# Microcontroller.net
KiCad netlist of a schematic drawn in Altium Designer
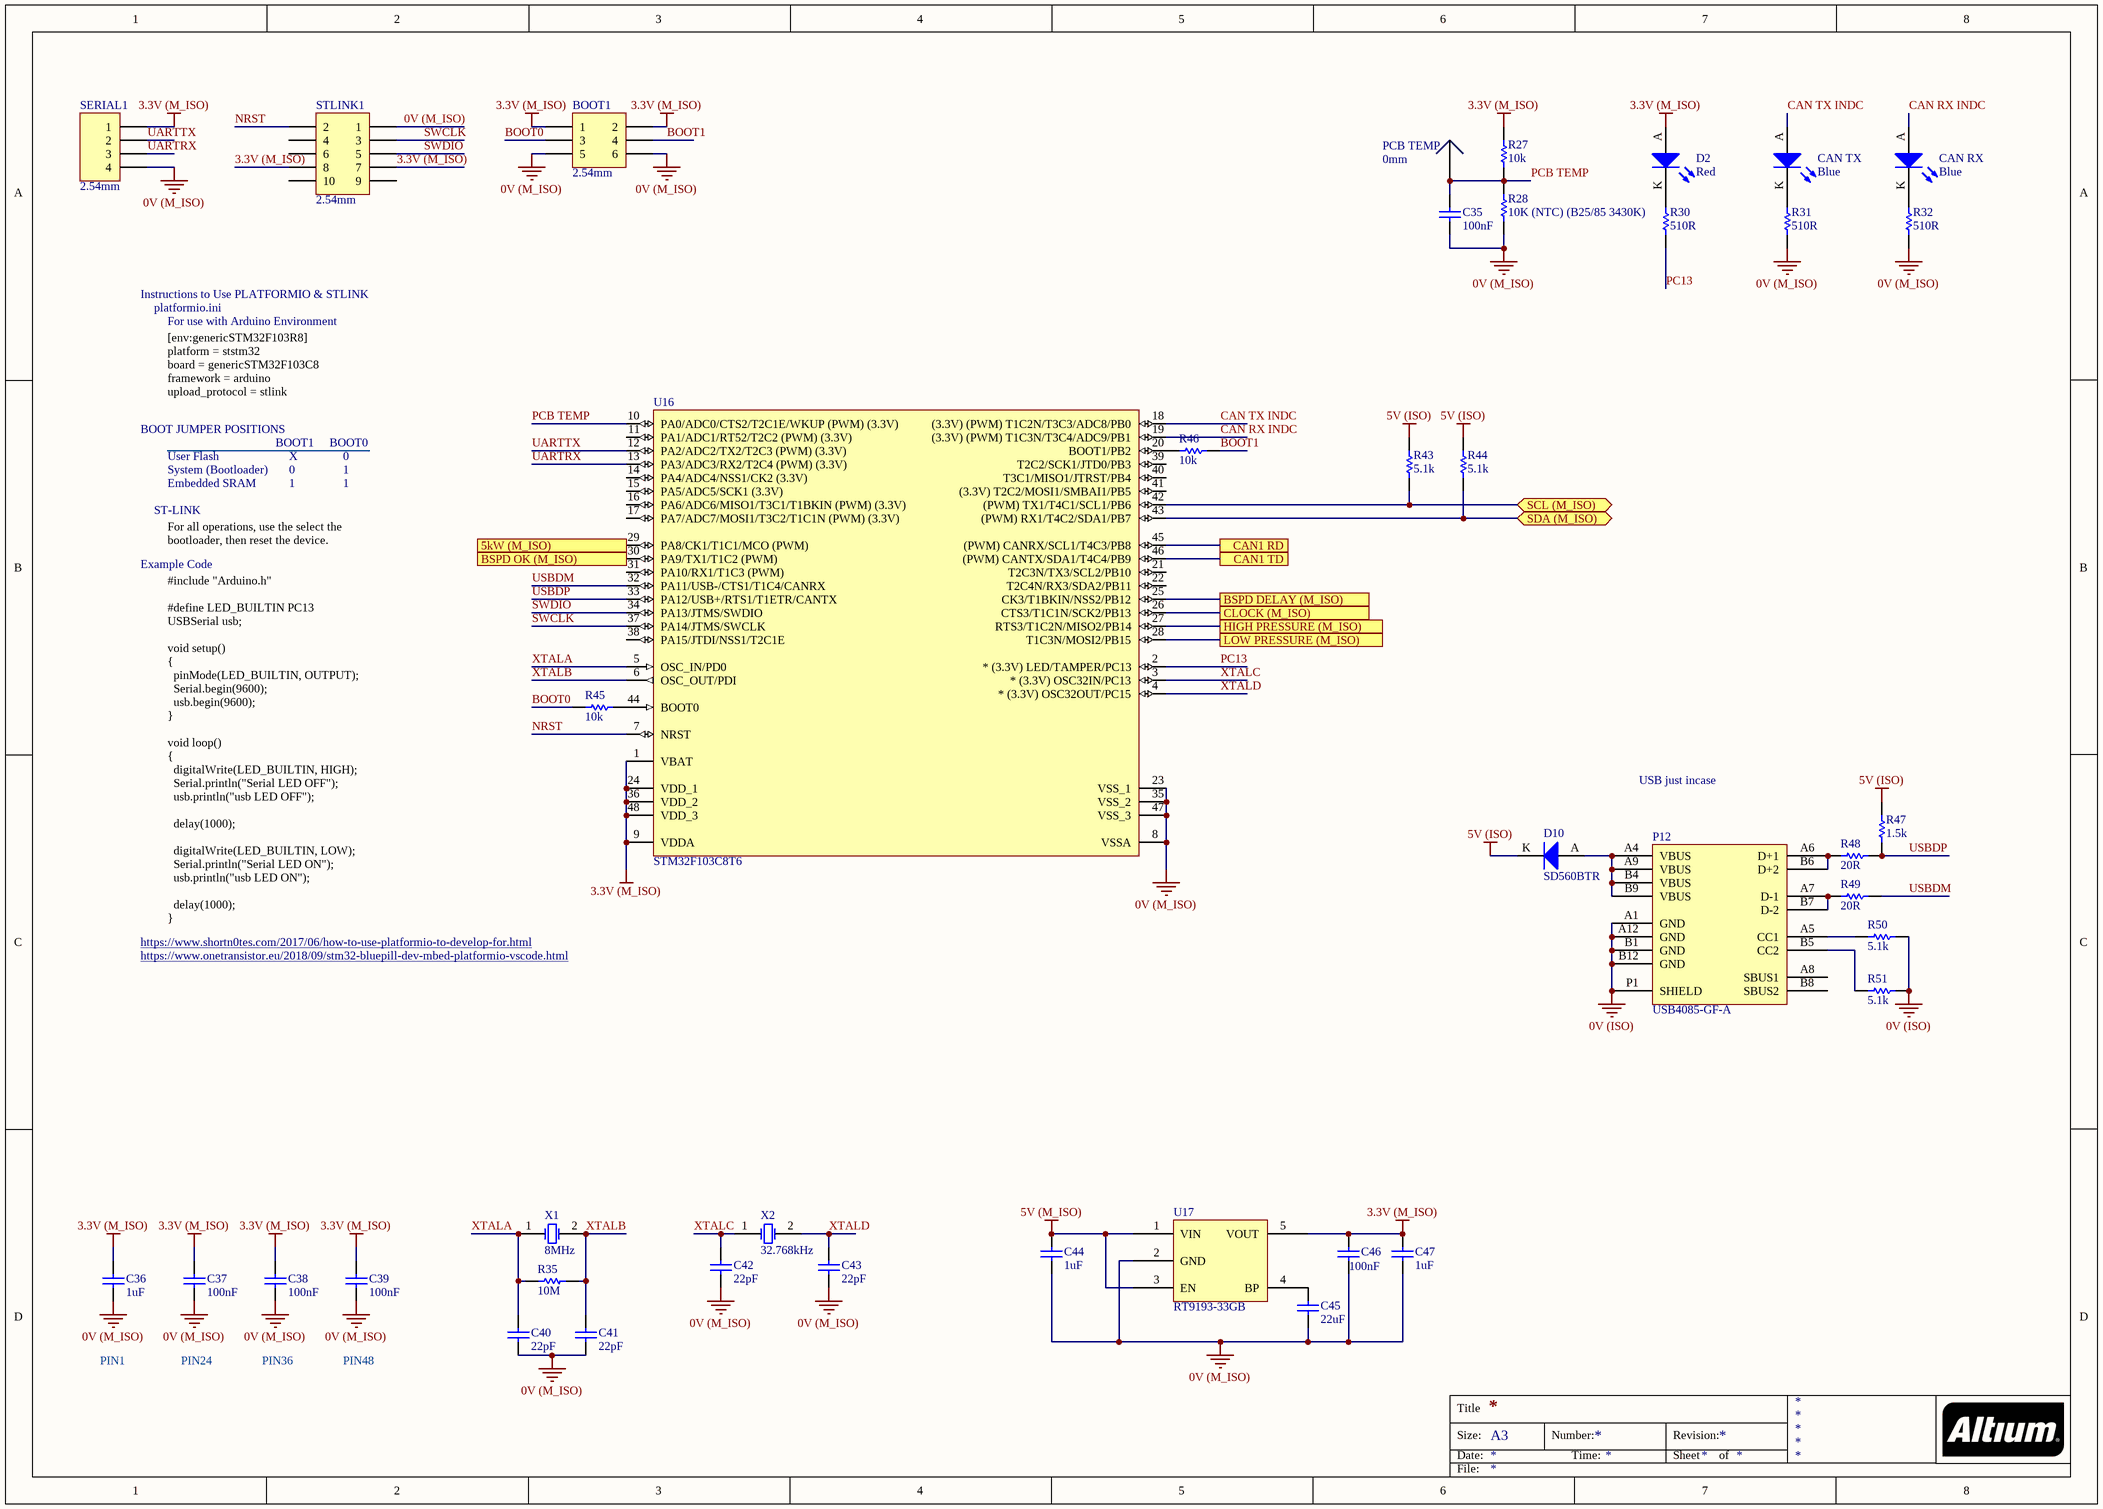
[diagram p0: Microcontroller.SchDoc]

(export (version "E")
  (design (tool "Eeschema 10.0.6"))
  (components
    (comp (ref "BOOT1")
      (value "2.54mm")
      (footprint "TH 2.54mm Header 2x3")
      (fields (field (name "PART NUMBER") "TH 2.54mm Header 2x3") (field (name "CONTACT") "NA"))
      (libsource (lib "ts_20-standard-connectors") (part "Header 2x3"))
    )
    (comp (ref "C35")
      (value "100nF")
      (footprint "0805")
      (fields
        (field (name "PART NUMBER") "GCM21BR71E104KA37L")
        (field (name "TOLERANCE") "10%")
        (field (name "MANUFACTURER") "muRata")
      )
      (libsource (lib "ts_20-standard-library") (part "Capacitor"))
    )
    (comp (ref "C36")
      (value "1uF")
      (footprint "0805")
      (fields
        (field (name "PART NUMBER") "AC0805KKX7R8BB105")
        (field (name "TOLERANCE") "10%")
        (field (name "MANUFACTURER") "YAGEO")
      )
      (libsource (lib "ts_20-standard-library") (part "Capacitor"))
    )
    (comp (ref "C37")
      (value "100nF")
      (footprint "0805")
      (fields
        (field (name "PART NUMBER") "GCM21BR71E104KA37L")
        (field (name "TOLERANCE") "10%")
        (field (name "MANUFACTURER") "muRata")
      )
      (libsource (lib "ts_20-standard-library") (part "Capacitor"))
    )
    (comp (ref "C38")
      (value "100nF")
      (footprint "0805")
      (fields
        (field (name "PART NUMBER") "GCM21BR71E104KA37L")
        (field (name "TOLERANCE") "10%")
        (field (name "MANUFACTURER") "muRata")
      )
      (libsource (lib "ts_20-standard-library") (part "Capacitor"))
    )
    (comp (ref "C39")
      (value "100nF")
      (footprint "0805")
      (fields
        (field (name "PART NUMBER") "GCM21BR71E104KA37L")
        (field (name "TOLERANCE") "10%")
        (field (name "MANUFACTURER") "muRata")
      )
      (libsource (lib "ts_20-standard-library") (part "Capacitor"))
    )
    (comp (ref "C40")
      (value "22pF")
      (footprint "0805")
      (fields
        (field (name "PART NUMBER") "GCM21B5C1H220JA37L")
        (field (name "TOLERANCE") "5%")
        (field (name "MANUFACTURER") "muRata")
      )
      (libsource (lib "ts_20-standard-library") (part "Capacitor"))
    )
    (comp (ref "C41")
      (value "22pF")
      (footprint "0805")
      (fields
        (field (name "PART NUMBER") "GCM21B5C1H220JA37L")
        (field (name "TOLERANCE") "5%")
        (field (name "MANUFACTURER") "muRata")
      )
      (libsource (lib "ts_20-standard-library") (part "Capacitor"))
    )
    (comp (ref "C42")
      (value "22pF")
      (footprint "0805")
      (fields
        (field (name "PART NUMBER") "GCM21B5C1H220JA37L")
        (field (name "TOLERANCE") "5%")
        (field (name "MANUFACTURER") "muRata")
      )
      (libsource (lib "ts_20-standard-library") (part "Capacitor"))
    )
    (comp (ref "C43")
      (value "22pF")
      (footprint "0805")
      (fields
        (field (name "PART NUMBER") "GCM21B5C1H220JA37L")
        (field (name "TOLERANCE") "5%")
        (field (name "MANUFACTURER") "muRata")
      )
      (libsource (lib "ts_20-standard-library") (part "Capacitor"))
    )
    (comp (ref "C44")
      (value "1uF")
      (footprint "0805")
      (fields
        (field (name "PART NUMBER") "AC0805KKX7R8BB105")
        (field (name "TOLERANCE") "10%")
        (field (name "MANUFACTURER") "YAGEO")
      )
      (libsource (lib "ts_20-standard-library") (part "Capacitor"))
    )
    (comp (ref "C45")
      (value "22uF")
      (footprint "0805")
      (fields
        (field (name "PART NUMBER") "GRM21BR61A226ME51L")
        (field (name "TOLERANCE") "20%")
        (field (name "MANUFACTURER") "muRata")
      )
      (libsource (lib "ts_20-standard-library") (part "Capacitor"))
    )
    (comp (ref "C46")
      (value "100nF")
      (footprint "0805")
      (fields
        (field (name "PART NUMBER") "GCM21BR71E104KA37L")
        (field (name "TOLERANCE") "10%")
        (field (name "MANUFACTURER") "muRata")
      )
      (libsource (lib "ts_20-standard-library") (part "Capacitor"))
    )
    (comp (ref "C47")
      (value "1uF")
      (footprint "0805")
      (fields
        (field (name "PART NUMBER") "AC0805KKX7R8BB105")
        (field (name "TOLERANCE") "10%")
        (field (name "MANUFACTURER") "YAGEO")
      )
      (libsource (lib "ts_20-standard-library") (part "Capacitor"))
    )
    (comp (ref "CAN RX")
      (value "Blue")
      (footprint "0805 LED")
      (description "LED BLUE CLEAR 2012 SMD")
      (fields
        (field (name "PART NUMBER") "SML-MN2BCTT86C")
        (field (name "MANUFACTURER") "ROHM Semiconductor")
      )
      (libsource (lib "ts_20-standard-library") (part "LED"))
    )
    (comp (ref "CAN TX")
      (value "Blue")
      (footprint "0805 LED")
      (description "LED BLUE CLEAR 2012 SMD")
      (fields
        (field (name "PART NUMBER") "SML-MN2BCTT86C")
        (field (name "MANUFACTURER") "ROHM Semiconductor")
      )
      (libsource (lib "ts_20-standard-library") (part "LED"))
    )
    (comp (ref "D2")
      (value "Red")
      (footprint "0805 LED")
      (description "Red LED Indication - Discrete 1.75V 0805 (2012 Metric)")
      (fields (field (name "PART NUMBER") "SML-210LTT86") (field (name "MANUFACTURER") "ROHM Semiconductor"))
      (libsource (lib "ts_20-standard-library") (part "LED"))
    )
    (comp (ref "D10")
      (value "SD560BTR")
      (footprint "SMB Diode")
      (description "1.2V_F 600V 5A SMB")
      (fields
        (field (name "MANUFACTURER") "SMC Diode Solutions")
        (field (name "DIGIKEY PART NUMBER") "1655-1530-2-ND")
      )
      (libsource (lib "ts_20-standard-library") (part "Diode"))
    )
    (comp (ref "P12")
      (value "USB4085-GF-A")
      (footprint "USB4085-GF-A")
      (description "USB - C (Type - C) USB 2.0 Receptacle Connector 16 Position Through Hole, Right Angle")
      (fields (field (name "DIGIKEY PART NUMBER") "2073-USB4085-GF-ACT-ND"))
      (libsource (lib "ts_20-standard-connectors") (part "USB4085-GF-A"))
    )
    (comp (ref "PCB TEMP")
      (value "0mm")
      (footprint "SMD Test Point")
      (fields (field (name "PART NUMBER") "SMD Test Point") (field (name "CONTACT") "NA"))
      (libsource (lib "ts_20-standard-connectors") (part "Test Point"))
    )
    (comp (ref "R27")
      (value "10k")
      (footprint "0805")
      (fields
        (field (name "PART NUMBER") "RC0805FR0710KL")
        (field (name "MANUFACTURER") "YAGEO")
        (field (name "TOLERANCE") "0.01")
      )
      (libsource (lib "ts_20-standard-library") (part "Resistor"))
    )
    (comp (ref "R28")
      (value "10K (NTC) (B25/85 3430K)")
      (footprint "0805")
      (fields
        (field (name "PART NUMBER") "NTCS0805E3103FLT")
        (field (name "MANUFACTURER") "Vishay Beyschlag")
        (field (name "TOLERANCE") "0.01")
      )
      (libsource (lib "ts_20-standard-library") (part "Resistor"))
    )
    (comp (ref "R30")
      (value "510R")
      (footprint "0805")
      (fields
        (field (name "PART NUMBER") "RC0805FR07510RL")
        (field (name "MANUFACTURER") "YAGEO")
        (field (name "TOLERANCE") "0.01")
      )
      (libsource (lib "ts_20-standard-library") (part "Resistor"))
    )
    (comp (ref "R31")
      (value "510R")
      (footprint "0805")
      (fields
        (field (name "PART NUMBER") "RC0805FR07510RL")
        (field (name "MANUFACTURER") "YAGEO")
        (field (name "TOLERANCE") "0.01")
      )
      (libsource (lib "ts_20-standard-library") (part "Resistor"))
    )
    (comp (ref "R32")
      (value "510R")
      (footprint "0805")
      (fields
        (field (name "PART NUMBER") "RC0805FR07510RL")
        (field (name "MANUFACTURER") "YAGEO")
        (field (name "TOLERANCE") "0.01")
      )
      (libsource (lib "ts_20-standard-library") (part "Resistor"))
    )
    (comp (ref "R35")
      (value "10M")
      (footprint "0805")
      (fields
        (field (name "PART NUMBER") "RC0805FR0710ML")
        (field (name "MANUFACTURER") "YAGEO")
        (field (name "TOLERANCE") "0.01")
      )
      (libsource (lib "ts_20-standard-library") (part "Resistor"))
    )
    (comp (ref "R43")
      (value "5.1k")
      (footprint "0805")
      (fields
        (field (name "PART NUMBER") "RC0805FR075K1L")
        (field (name "MANUFACTURER") "YAGEO")
        (field (name "TOLERANCE") "0.01")
      )
      (libsource (lib "ts_20-standard-library") (part "Resistor"))
    )
    (comp (ref "R44")
      (value "5.1k")
      (footprint "0805")
      (fields
        (field (name "PART NUMBER") "RC0805FR075K1L")
        (field (name "MANUFACTURER") "YAGEO")
        (field (name "TOLERANCE") "0.01")
      )
      (libsource (lib "ts_20-standard-library") (part "Resistor"))
    )
    (comp (ref "R45")
      (value "10k")
      (footprint "0805")
      (fields
        (field (name "PART NUMBER") "RC0805FR0710KL")
        (field (name "MANUFACTURER") "YAGEO")
        (field (name "TOLERANCE") "0.01")
      )
      (libsource (lib "ts_20-standard-library") (part "Resistor"))
    )
    (comp (ref "R46")
      (value "10k")
      (footprint "0805")
      (fields
        (field (name "PART NUMBER") "RC0805FR0710KL")
        (field (name "MANUFACTURER") "YAGEO")
        (field (name "TOLERANCE") "0.01")
      )
      (libsource (lib "ts_20-standard-library") (part "Resistor"))
    )
    (comp (ref "R47")
      (value "1.5k")
      (footprint "0805")
      (fields
        (field (name "PART NUMBER") "RC0805FR071K5L")
        (field (name "MANUFACTURER") "YAGEO")
        (field (name "TOLERANCE") "0.01")
      )
      (libsource (lib "ts_20-standard-library") (part "Resistor"))
    )
    (comp (ref "R48")
      (value "20R")
      (footprint "0805")
      (fields
        (field (name "PART NUMBER") "RC0805FR0720RL")
        (field (name "MANUFACTURER") "YAGEO")
        (field (name "TOLERANCE") "0.01")
      )
      (libsource (lib "ts_20-standard-library") (part "Resistor"))
    )
    (comp (ref "R49")
      (value "20R")
      (footprint "0805")
      (fields
        (field (name "PART NUMBER") "RC0805FR0720RL")
        (field (name "MANUFACTURER") "YAGEO")
        (field (name "TOLERANCE") "0.01")
      )
      (libsource (lib "ts_20-standard-library") (part "Resistor"))
    )
    (comp (ref "R50")
      (value "5.1k")
      (footprint "0805")
      (fields
        (field (name "PART NUMBER") "RC0805FR075K1L")
        (field (name "MANUFACTURER") "YAGEO")
        (field (name "TOLERANCE") "0.01")
      )
      (libsource (lib "ts_20-standard-library") (part "Resistor"))
    )
    (comp (ref "R51")
      (value "5.1k")
      (footprint "0805")
      (fields
        (field (name "PART NUMBER") "RC0805FR075K1L")
        (field (name "MANUFACTURER") "YAGEO")
        (field (name "TOLERANCE") "0.01")
      )
      (libsource (lib "ts_20-standard-library") (part "Resistor"))
    )
    (comp (ref "SERIAL1")
      (value "2.54mm")
      (footprint "TH 2.54mm Header 1x4")
      (fields (field (name "PART NUMBER") "TH 2.54mm Header 1x4") (field (name "CONTACT") "NA"))
      (libsource (lib "ts_20-standard-connectors") (part "Header 1x4"))
    )
    (comp (ref "STLINK1")
      (value "2.54mm")
      (footprint "TH 2.54mm Header 2x5")
      (fields (field (name "PART NUMBER") "TH 2.54mm Header 2x5") (field (name "CONTACT") "NA"))
      (libsource (lib "ts_20-standard-connectors") (part "Header 2x5"))
    )
    (comp (ref "U16")
      (value "STM32F103C8T6")
      (footprint "STM 48-LQFP")
      (description "ARM® Cortex®-M3 STM32F1 Microcontroller IC 32-Bit 72MHz 64KB (64K x 8) FLASH")
      (fields
        (field (name "MANUFACTURER") "STMicroelectronics")
        (field (name "DIGIKEY PART NUMBER") "497-6063-ND")
      )
      (libsource (lib "ts_20-standard-library") (part "STM32F103C8T6"))
    )
    (comp (ref "U17")
      (value "RT9193-33GB")
      (footprint "RICHTEK SOT-23-5")
      (description "IC REG LINEAR 3.3V 300MA SOT23-5")
      (fields (field (name "MANUFACTURER") "Richtek") (field (name "DIGIKEY PART NUMBER") "1028-1014-1-ND"))
      (libsource (lib "ts_20-standard-library") (part "RT9193-33GB"))
    )
    (comp (ref "X1")
      (value "8MHz")
      (footprint "Abracon HC-49/US")
      (fields
        (field (name "PART NUMBER") "ABLS-8.000MHZ-B4-T")
        (field (name "MANUFACTURER") "Abracon LLC")
        (field (name "DIGIKEY PART NUMBER") "535-10212-2-ND")
      )
      (libsource (lib "ts_20-standard-library") (part "Crystal"))
    )
    (comp (ref "X2")
      (value "32.768kHz")
      (footprint "EPSON 2-SMD")
      (fields
        (field (name "PART NUMBER") "FC-135 32.7680KA-A5")
        (field (name "MANUFACTURER") "EPSON")
        (field (name "DIGIKEY PART NUMBER") "SER4103TR-ND")
      )
      (libsource (lib "ts_20-standard-library") (part "Crystal"))
    )
  )
  (nets
    (net (code "1") (name "/5kW (M_ISO)") (class "Default")
      (node (ref "U16") (pin "29") (pinfunction "PA8/CK1/T1C1/MCO_(PWM)_29") (pintype "bidirectional"))
    )
    (net (code "2") (name "/BOOT0") (class "Default")
      (node (ref "BOOT1") (pin "3") (pinfunction "3_3") (pintype "passive"))
      (node (ref "R45") (pin "1") (pinfunction "1_1") (pintype "passive"))
    )
    (net (code "3") (name "/BOOT1") (class "Default")
      (node (ref "BOOT1") (pin "4") (pinfunction "4_4") (pintype "passive"))
      (node (ref "R46") (pin "2") (pinfunction "2_2") (pintype "passive"))
    )
    (net (code "4") (name "/BSPD DELAY (M_ISO)") (class "Default")
      (node (ref "U16") (pin "25") (pinfunction "CK3/T1BKIN/NSS2/PB12_25") (pintype "bidirectional"))
    )
    (net (code "5") (name "/BSPD OK (M_ISO)") (class "Default")
      (node (ref "U16") (pin "30") (pinfunction "PA9/TX1/T1C2_(PWM)_30") (pintype "bidirectional"))
    )
    (net (code "6") (name "/CAN RX INDC") (class "Default")
      (node (ref "CAN RX") (pin "A") (pinfunction "A_A") (pintype "passive"))
      (node (ref "U16") (pin "19") (pinfunction "(3.3V)_(PWM)_T1C3N/T3C4/ADC9/PB1_19") (pintype "bidirectional"))
    )
    (net (code "7") (name "/CAN TX INDC") (class "Default")
      (node (ref "CAN TX") (pin "A") (pinfunction "A_A") (pintype "passive"))
      (node (ref "U16") (pin "18") (pinfunction "(3.3V)_(PWM)_T1C2N/T3C3/ADC8/PB0_18") (pintype "bidirectional"))
    )
    (net (code "8") (name "/CAN1 RD") (class "Default")
      (node (ref "U16") (pin "45") (pinfunction "(PWM)_CANRX/SCL1/T4C3/PB8_45") (pintype "bidirectional"))
    )
    (net (code "9") (name "/CAN1 TD") (class "Default")
      (node (ref "U16") (pin "46") (pinfunction "(PWM)_CANTX/SDA1/T4C4/PB9_46") (pintype "bidirectional"))
    )
    (net (code "10") (name "/CLOCK (M_ISO)") (class "Default")
      (node (ref "U16") (pin "26") (pinfunction "CTS3/T1C1N/SCK2/PB13_26") (pintype "bidirectional"))
    )
    (net (code "11") (name "/HIGH PRESSURE (M_ISO)") (class "Default")
      (node (ref "U16") (pin "27") (pinfunction "RTS3/T1C2N/MISO2/PB14_27") (pintype "bidirectional"))
    )
    (net (code "12") (name "/LOW PRESSURE (M_ISO)") (class "Default")
      (node (ref "U16") (pin "28") (pinfunction "T1C3N/MOSI2/PB15_28") (pintype "bidirectional"))
    )
    (net (code "13") (name "/NRST") (class "Default")
      (node (ref "STLINK1") (pin "2") (pinfunction "2_2") (pintype "passive"))
      (node (ref "U16") (pin "7") (pinfunction "NRST_7") (pintype "bidirectional"))
    )
    (net (code "14") (name "/PC13") (class "Default")
      (node (ref "R30") (pin "1") (pinfunction "1_1") (pintype "passive"))
      (node (ref "U16") (pin "2") (pinfunction "*_(3.3V)_LED/TAMPER/PC13_2") (pintype "bidirectional"))
    )
    (net (code "15") (name "/PCB TEMP") (class "Default")
      (node (ref "C35") (pin "2") (pinfunction "2_2") (pintype "passive"))
      (node (ref "PCB TEMP") (pin "1") (pinfunction "1_1") (pintype "passive"))
      (node (ref "R27") (pin "1") (pinfunction "1_1") (pintype "passive"))
      (node (ref "R28") (pin "2") (pinfunction "2_2") (pintype "passive"))
      (node (ref "U16") (pin "10") (pinfunction "PA0/ADC0/CTS2/T2C1E/WKUP_(PWM)_(3.3V)_10") (pintype "bidirectional"))
    )
    (net (code "16") (name "/SCL (M_ISO)") (class "Default")
      (node (ref "R43") (pin "1") (pinfunction "1_1") (pintype "passive"))
      (node (ref "U16") (pin "42") (pinfunction "(PWM)_TX1/T4C1/SCL1/PB6_42") (pintype "bidirectional"))
    )
    (net (code "17") (name "/SDA (M_ISO)") (class "Default")
      (node (ref "R44") (pin "1") (pinfunction "1_1") (pintype "passive"))
      (node (ref "U16") (pin "43") (pinfunction "(PWM)_RX1/T4C2/SDA1/PB7_43") (pintype "bidirectional"))
    )
    (net (code "18") (name "/SWCLK") (class "Default")
      (node (ref "STLINK1") (pin "3") (pinfunction "3_3") (pintype "passive"))
      (node (ref "U16") (pin "37") (pinfunction "PA14/JTMS/SWCLK_37") (pintype "bidirectional"))
    )
    (net (code "19") (name "/SWDIO") (class "Default")
      (node (ref "STLINK1") (pin "5") (pinfunction "5_5") (pintype "passive"))
      (node (ref "U16") (pin "34") (pinfunction "PA13/JTMS/SWDIO_34") (pintype "bidirectional"))
    )
    (net (code "20") (name "/UARTRX") (class "Default")
      (node (ref "SERIAL1") (pin "3") (pinfunction "3_3") (pintype "passive"))
      (node (ref "U16") (pin "13") (pinfunction "PA3/ADC3/RX2/T2C4_(PWM)_(3.3V)_13") (pintype "bidirectional"))
    )
    (net (code "21") (name "/UARTTX") (class "Default")
      (node (ref "SERIAL1") (pin "2") (pinfunction "2_2") (pintype "passive"))
      (node (ref "U16") (pin "12") (pinfunction "PA2/ADC2/TX2/T2C3_(PWM)_(3.3V)_12") (pintype "bidirectional"))
    )
    (net (code "22") (name "/USBDM") (class "Default")
      (node (ref "R49") (pin "2") (pinfunction "2_2") (pintype "passive"))
      (node (ref "U16") (pin "32") (pinfunction "PA11/USB-/CTS1/T1C4/CANRX_32") (pintype "bidirectional"))
    )
    (net (code "23") (name "/USBDP") (class "Default")
      (node (ref "R47") (pin "1") (pinfunction "1_1") (pintype "passive"))
      (node (ref "R48") (pin "2") (pinfunction "2_2") (pintype "passive"))
      (node (ref "U16") (pin "33") (pinfunction "PA12/USB+/RTS1/T1ETR/CANTX_33") (pintype "bidirectional"))
    )
    (net (code "24") (name "/XTALA") (class "Default")
      (node (ref "C40") (pin "2") (pinfunction "2_2") (pintype "passive"))
      (node (ref "R35") (pin "1") (pinfunction "1_1") (pintype "passive"))
      (node (ref "U16") (pin "5") (pinfunction "OSC_IN/PD0_5") (pintype "input"))
      (node (ref "X1") (pin "1") (pinfunction "OSC1_1") (pintype "passive"))
    )
    (net (code "25") (name "/XTALB") (class "Default")
      (node (ref "C41") (pin "2") (pinfunction "2_2") (pintype "passive"))
      (node (ref "R35") (pin "2") (pinfunction "2_2") (pintype "passive"))
      (node (ref "U16") (pin "6") (pinfunction "OSC_OUT/PDI_6") (pintype "output"))
      (node (ref "X1") (pin "2") (pinfunction "OSC2_2") (pintype "passive"))
    )
    (net (code "26") (name "/XTALC") (class "Default")
      (node (ref "C42") (pin "2") (pinfunction "2_2") (pintype "passive"))
      (node (ref "U16") (pin "3") (pinfunction "*_(3.3V)_OSC32IN/PC13_3") (pintype "bidirectional"))
      (node (ref "X2") (pin "1") (pinfunction "OSC1_1") (pintype "passive"))
    )
    (net (code "27") (name "/XTALD") (class "Default")
      (node (ref "C43") (pin "2") (pinfunction "2_2") (pintype "passive"))
      (node (ref "U16") (pin "4") (pinfunction "*_(3.3V)_OSC32OUT/PC15_4") (pintype "bidirectional"))
      (node (ref "X2") (pin "2") (pinfunction "OSC2_2") (pintype "passive"))
    )
    (net (code "28") (name "0V (ISO)") (class "Default")
      (node (ref "P12") (pin "A1") (pinfunction "GND_A1") (pintype "passive"))
      (node (ref "P12") (pin "A12") (pinfunction "GND_A12") (pintype "passive"))
      (node (ref "P12") (pin "B1") (pinfunction "GND_B1") (pintype "passive"))
      (node (ref "P12") (pin "B12") (pinfunction "GND_B12") (pintype "passive"))
      (node (ref "P12") (pin "P1") (pinfunction "SHIELD_P1") (pintype "passive"))
      (node (ref "R50") (pin "2") (pinfunction "2_2") (pintype "passive"))
      (node (ref "R51") (pin "2") (pinfunction "2_2") (pintype "passive"))
    )
    (net (code "29") (name "0V (M_ISO)") (class "Default")
      (node (ref "BOOT1") (pin "5") (pinfunction "5_5") (pintype "passive"))
      (node (ref "BOOT1") (pin "6") (pinfunction "6_6") (pintype "passive"))
      (node (ref "C35") (pin "1") (pinfunction "1_1") (pintype "passive"))
      (node (ref "C36") (pin "1") (pinfunction "1_1") (pintype "passive"))
      (node (ref "C37") (pin "1") (pinfunction "1_1") (pintype "passive"))
      (node (ref "C38") (pin "1") (pinfunction "1_1") (pintype "passive"))
      (node (ref "C39") (pin "1") (pinfunction "1_1") (pintype "passive"))
      (node (ref "C40") (pin "1") (pinfunction "1_1") (pintype "passive"))
      (node (ref "C41") (pin "1") (pinfunction "1_1") (pintype "passive"))
      (node (ref "C42") (pin "1") (pinfunction "1_1") (pintype "passive"))
      (node (ref "C43") (pin "1") (pinfunction "1_1") (pintype "passive"))
      (node (ref "C44") (pin "1") (pinfunction "1_1") (pintype "passive"))
      (node (ref "C45") (pin "1") (pinfunction "1_1") (pintype "passive"))
      (node (ref "C46") (pin "1") (pinfunction "1_1") (pintype "passive"))
      (node (ref "C47") (pin "1") (pinfunction "1_1") (pintype "passive"))
      (node (ref "R28") (pin "1") (pinfunction "1_1") (pintype "passive"))
      (node (ref "R31") (pin "1") (pinfunction "1_1") (pintype "passive"))
      (node (ref "R32") (pin "1") (pinfunction "1_1") (pintype "passive"))
      (node (ref "SERIAL1") (pin "4") (pinfunction "4_4") (pintype "passive"))
      (node (ref "STLINK1") (pin "1") (pinfunction "1_1") (pintype "passive"))
      (node (ref "U16") (pin "23") (pinfunction "VSS_1_23") (pintype "power_in"))
      (node (ref "U16") (pin "35") (pinfunction "VSS_2_35") (pintype "power_in"))
      (node (ref "U16") (pin "47") (pinfunction "VSS_3_47") (pintype "power_in"))
      (node (ref "U16") (pin "8") (pinfunction "VSSA_8") (pintype "power_in"))
      (node (ref "U17") (pin "2") (pinfunction "GND_2") (pintype "passive"))
    )
    (net (code "30") (name "3.3V (M_ISO)") (class "Default")
      (node (ref "BOOT1") (pin "1") (pinfunction "1_1") (pintype "passive"))
      (node (ref "BOOT1") (pin "2") (pinfunction "2_2") (pintype "passive"))
      (node (ref "C36") (pin "2") (pinfunction "2_2") (pintype "passive"))
      (node (ref "C37") (pin "2") (pinfunction "2_2") (pintype "passive"))
      (node (ref "C38") (pin "2") (pinfunction "2_2") (pintype "passive"))
      (node (ref "C39") (pin "2") (pinfunction "2_2") (pintype "passive"))
      (node (ref "C46") (pin "2") (pinfunction "2_2") (pintype "passive"))
      (node (ref "C47") (pin "2") (pinfunction "2_2") (pintype "passive"))
      (node (ref "D2") (pin "A") (pinfunction "A_A") (pintype "passive"))
      (node (ref "R27") (pin "2") (pinfunction "2_2") (pintype "passive"))
      (node (ref "SERIAL1") (pin "1") (pinfunction "1_1") (pintype "passive"))
      (node (ref "STLINK1") (pin "7") (pinfunction "7_7") (pintype "passive"))
      (node (ref "STLINK1") (pin "8") (pinfunction "8_8") (pintype "passive"))
      (node (ref "U16") (pin "1") (pinfunction "VBAT_1") (pintype "power_in"))
      (node (ref "U16") (pin "24") (pinfunction "VDD_1_24") (pintype "power_in"))
      (node (ref "U16") (pin "36") (pinfunction "VDD_2_36") (pintype "power_in"))
      (node (ref "U16") (pin "48") (pinfunction "VDD_3_48") (pintype "power_in"))
      (node (ref "U16") (pin "9") (pinfunction "VDDA_9") (pintype "power_in"))
      (node (ref "U17") (pin "5") (pinfunction "VOUT_5") (pintype "passive"))
    )
    (net (code "31") (name "5V (ISO)") (class "Default")
      (node (ref "D10") (pin "K") (pinfunction "K_K") (pintype "passive"))
      (node (ref "R43") (pin "2") (pinfunction "2_2") (pintype "passive"))
      (node (ref "R44") (pin "2") (pinfunction "2_2") (pintype "passive"))
      (node (ref "R47") (pin "2") (pinfunction "2_2") (pintype "passive"))
    )
    (net (code "32") (name "5V (M_ISO)") (class "Default")
      (node (ref "C44") (pin "2") (pinfunction "2_2") (pintype "passive"))
      (node (ref "U17") (pin "1") (pinfunction "VIN_1") (pintype "passive"))
      (node (ref "U17") (pin "3") (pinfunction "EN_3") (pintype "passive"))
    )
    (net (code "33") (name "Net-(CAN RX-PadK)") (class "Default")
      (node (ref "CAN RX") (pin "K") (pinfunction "K_K") (pintype "passive"))
      (node (ref "R32") (pin "2") (pinfunction "2_2") (pintype "passive"))
    )
    (net (code "34") (name "Net-(CAN TX-PadK)") (class "Default")
      (node (ref "CAN TX") (pin "K") (pinfunction "K_K") (pintype "passive"))
      (node (ref "R31") (pin "2") (pinfunction "2_2") (pintype "passive"))
    )
    (net (code "35") (name "Net-(D2-PadK)") (class "Default")
      (node (ref "D2") (pin "K") (pinfunction "K_K") (pintype "passive"))
      (node (ref "R30") (pin "2") (pinfunction "2_2") (pintype "passive"))
    )
    (net (code "36") (name "Net-(D10-PadA)") (class "Default")
      (node (ref "D10") (pin "A") (pinfunction "A_A") (pintype "passive"))
      (node (ref "P12") (pin "A4") (pinfunction "VBUS_A4") (pintype "passive"))
      (node (ref "P12") (pin "A9") (pinfunction "VBUS_A9") (pintype "passive"))
      (node (ref "P12") (pin "B4") (pinfunction "VBUS_B4") (pintype "passive"))
      (node (ref "P12") (pin "B9") (pinfunction "VBUS_B9") (pintype "passive"))
    )
    (net (code "37") (name "Net-(P12-CC1)") (class "Default")
      (node (ref "P12") (pin "A5") (pinfunction "CC1_A5") (pintype "passive"))
      (node (ref "R50") (pin "1") (pinfunction "1_1") (pintype "passive"))
    )
    (net (code "38") (name "Net-(P12-CC2)") (class "Default")
      (node (ref "P12") (pin "B5") (pinfunction "CC2_B5") (pintype "passive"))
      (node (ref "R51") (pin "1") (pinfunction "1_1") (pintype "passive"))
    )
    (net (code "39") (name "Net-(P12-D+1)") (class "Default")
      (node (ref "P12") (pin "A6") (pinfunction "D+1_A6") (pintype "passive"))
      (node (ref "P12") (pin "B6") (pinfunction "D+2_B6") (pintype "passive"))
      (node (ref "R48") (pin "1") (pinfunction "1_1") (pintype "passive"))
    )
    (net (code "40") (name "Net-(P12-D-1)") (class "Default")
      (node (ref "P12") (pin "A7") (pinfunction "D-1_A7") (pintype "passive"))
      (node (ref "P12") (pin "B7") (pinfunction "D-2_B7") (pintype "passive"))
      (node (ref "R49") (pin "1") (pinfunction "1_1") (pintype "passive"))
    )
    (net (code "41") (name "Net-(U16-BOOT0)") (class "Default")
      (node (ref "R45") (pin "2") (pinfunction "2_2") (pintype "passive"))
      (node (ref "U16") (pin "44") (pinfunction "BOOT0_44") (pintype "input"))
    )
    (net (code "42") (name "Net-(U16-BOOT1{slash}PB2)") (class "Default")
      (node (ref "R46") (pin "1") (pinfunction "1_1") (pintype "passive"))
      (node (ref "U16") (pin "20") (pinfunction "BOOT1/PB2_20") (pintype "bidirectional"))
    )
    (net (code "43") (name "Net-(U17-BP)") (class "Default")
      (node (ref "C45") (pin "2") (pinfunction "2_2") (pintype "passive"))
      (node (ref "U17") (pin "4") (pinfunction "BP_4") (pintype "passive"))
    )
    (net (code "44") (name "unconnected-(P12-SBUS1-PadA8)") (class "Default")
      (node (ref "P12") (pin "A8") (pinfunction "SBUS1_A8") (pintype "passive"))
    )
    (net (code "45") (name "unconnected-(P12-SBUS2-PadB8)") (class "Default")
      (node (ref "P12") (pin "B8") (pinfunction "SBUS2_B8") (pintype "passive"))
    )
    (net (code "46") (name "unconnected-(STLINK1-Pad4)") (class "Default")
      (node (ref "STLINK1") (pin "4") (pinfunction "4_4") (pintype "passive"))
    )
    (net (code "47") (name "unconnected-(STLINK1-Pad6)") (class "Default")
      (node (ref "STLINK1") (pin "6") (pinfunction "6_6") (pintype "passive"))
    )
    (net (code "48") (name "unconnected-(STLINK1-Pad9)") (class "Default")
      (node (ref "STLINK1") (pin "9") (pinfunction "9_9") (pintype "passive"))
    )
    (net (code "49") (name "unconnected-(STLINK1-Pad10)") (class "Default")
      (node (ref "STLINK1") (pin "10") (pinfunction "10_10") (pintype "passive"))
    )
    (net (code "50") (name "unconnected-(U16-(3.3V)_T2C2{slash}MOSI1{slash}SMBAI1{slash}PB5-Pad41)") (class "Default")
      (node (ref "U16") (pin "41") (pinfunction "(3.3V)_T2C2/MOSI1/SMBAI1/PB5_41") (pintype "bidirectional"))
    )
    (net (code "51") (name "unconnected-(U16-PA1{slash}ADC1{slash}RT52{slash}T2C2_(PWM)_(3.3V)-Pad11)") (class "Default")
      (node (ref "U16") (pin "11") (pinfunction "PA1/ADC1/RT52/T2C2_(PWM)_(3.3V)_11") (pintype "bidirectional"))
    )
    (net (code "52") (name "unconnected-(U16-PA4{slash}ADC4{slash}NSS1{slash}CK2_(3.3V)-Pad14)") (class "Default")
      (node (ref "U16") (pin "14") (pinfunction "PA4/ADC4/NSS1/CK2_(3.3V)_14") (pintype "bidirectional"))
    )
    (net (code "53") (name "unconnected-(U16-PA5{slash}ADC5{slash}SCK1_(3.3V)-Pad15)") (class "Default")
      (node (ref "U16") (pin "15") (pinfunction "PA5/ADC5/SCK1_(3.3V)_15") (pintype "bidirectional"))
    )
    (net (code "54") (name "unconnected-(U16-PA6{slash}ADC6{slash}MISO1{slash}T3C1{slash}T1BKIN_(PWM)_(3.3V)-Pad16)") (class "Default")
      (node (ref "U16") (pin "16") (pinfunction "PA6/ADC6/MISO1/T3C1/T1BKIN_(PWM)_(3.3V)_16") (pintype "bidirectional"))
    )
    (net (code "55") (name "unconnected-(U16-PA7{slash}ADC7{slash}MOSI1{slash}T3C2{slash}T1C1N_(PWM)_(3.3V)-Pad17)") (class "Default")
      (node (ref "U16") (pin "17") (pinfunction "PA7/ADC7/MOSI1/T3C2/T1C1N_(PWM)_(3.3V)_17") (pintype "bidirectional"))
    )
    (net (code "56") (name "unconnected-(U16-PA10{slash}RX1{slash}T1C3_(PWM)-Pad31)") (class "Default")
      (node (ref "U16") (pin "31") (pinfunction "PA10/RX1/T1C3_(PWM)_31") (pintype "bidirectional"))
    )
    (net (code "57") (name "unconnected-(U16-PA15{slash}JTDI{slash}NSS1{slash}T2C1E-Pad38)") (class "Default")
      (node (ref "U16") (pin "38") (pinfunction "PA15/JTDI/NSS1/T2C1E_38") (pintype "bidirectional"))
    )
    (net (code "58") (name "unconnected-(U16-T2C2{slash}SCK1{slash}JTD0{slash}PB3-Pad39)") (class "Default")
      (node (ref "U16") (pin "39") (pinfunction "T2C2/SCK1/JTD0/PB3_39") (pintype "bidirectional"))
    )
    (net (code "59") (name "unconnected-(U16-T2C3N{slash}TX3{slash}SCL2{slash}PB10-Pad21)") (class "Default")
      (node (ref "U16") (pin "21") (pinfunction "T2C3N/TX3/SCL2/PB10_21") (pintype "bidirectional"))
    )
    (net (code "60") (name "unconnected-(U16-T2C4N{slash}RX3{slash}SDA2{slash}PB11-Pad22)") (class "Default")
      (node (ref "U16") (pin "22") (pinfunction "T2C4N/RX3/SDA2/PB11_22") (pintype "bidirectional"))
    )
    (net (code "61") (name "unconnected-(U16-T3C1{slash}MISO1{slash}JTRST{slash}PB4-Pad40)") (class "Default")
      (node (ref "U16") (pin "40") (pinfunction "T3C1/MISO1/JTRST/PB4_40") (pintype "bidirectional"))
    )
  )
)
